# SCH_Sensor_circuit_design_2023-04-27.net
KiCad netlist of a schematic drawn in EasyEDA
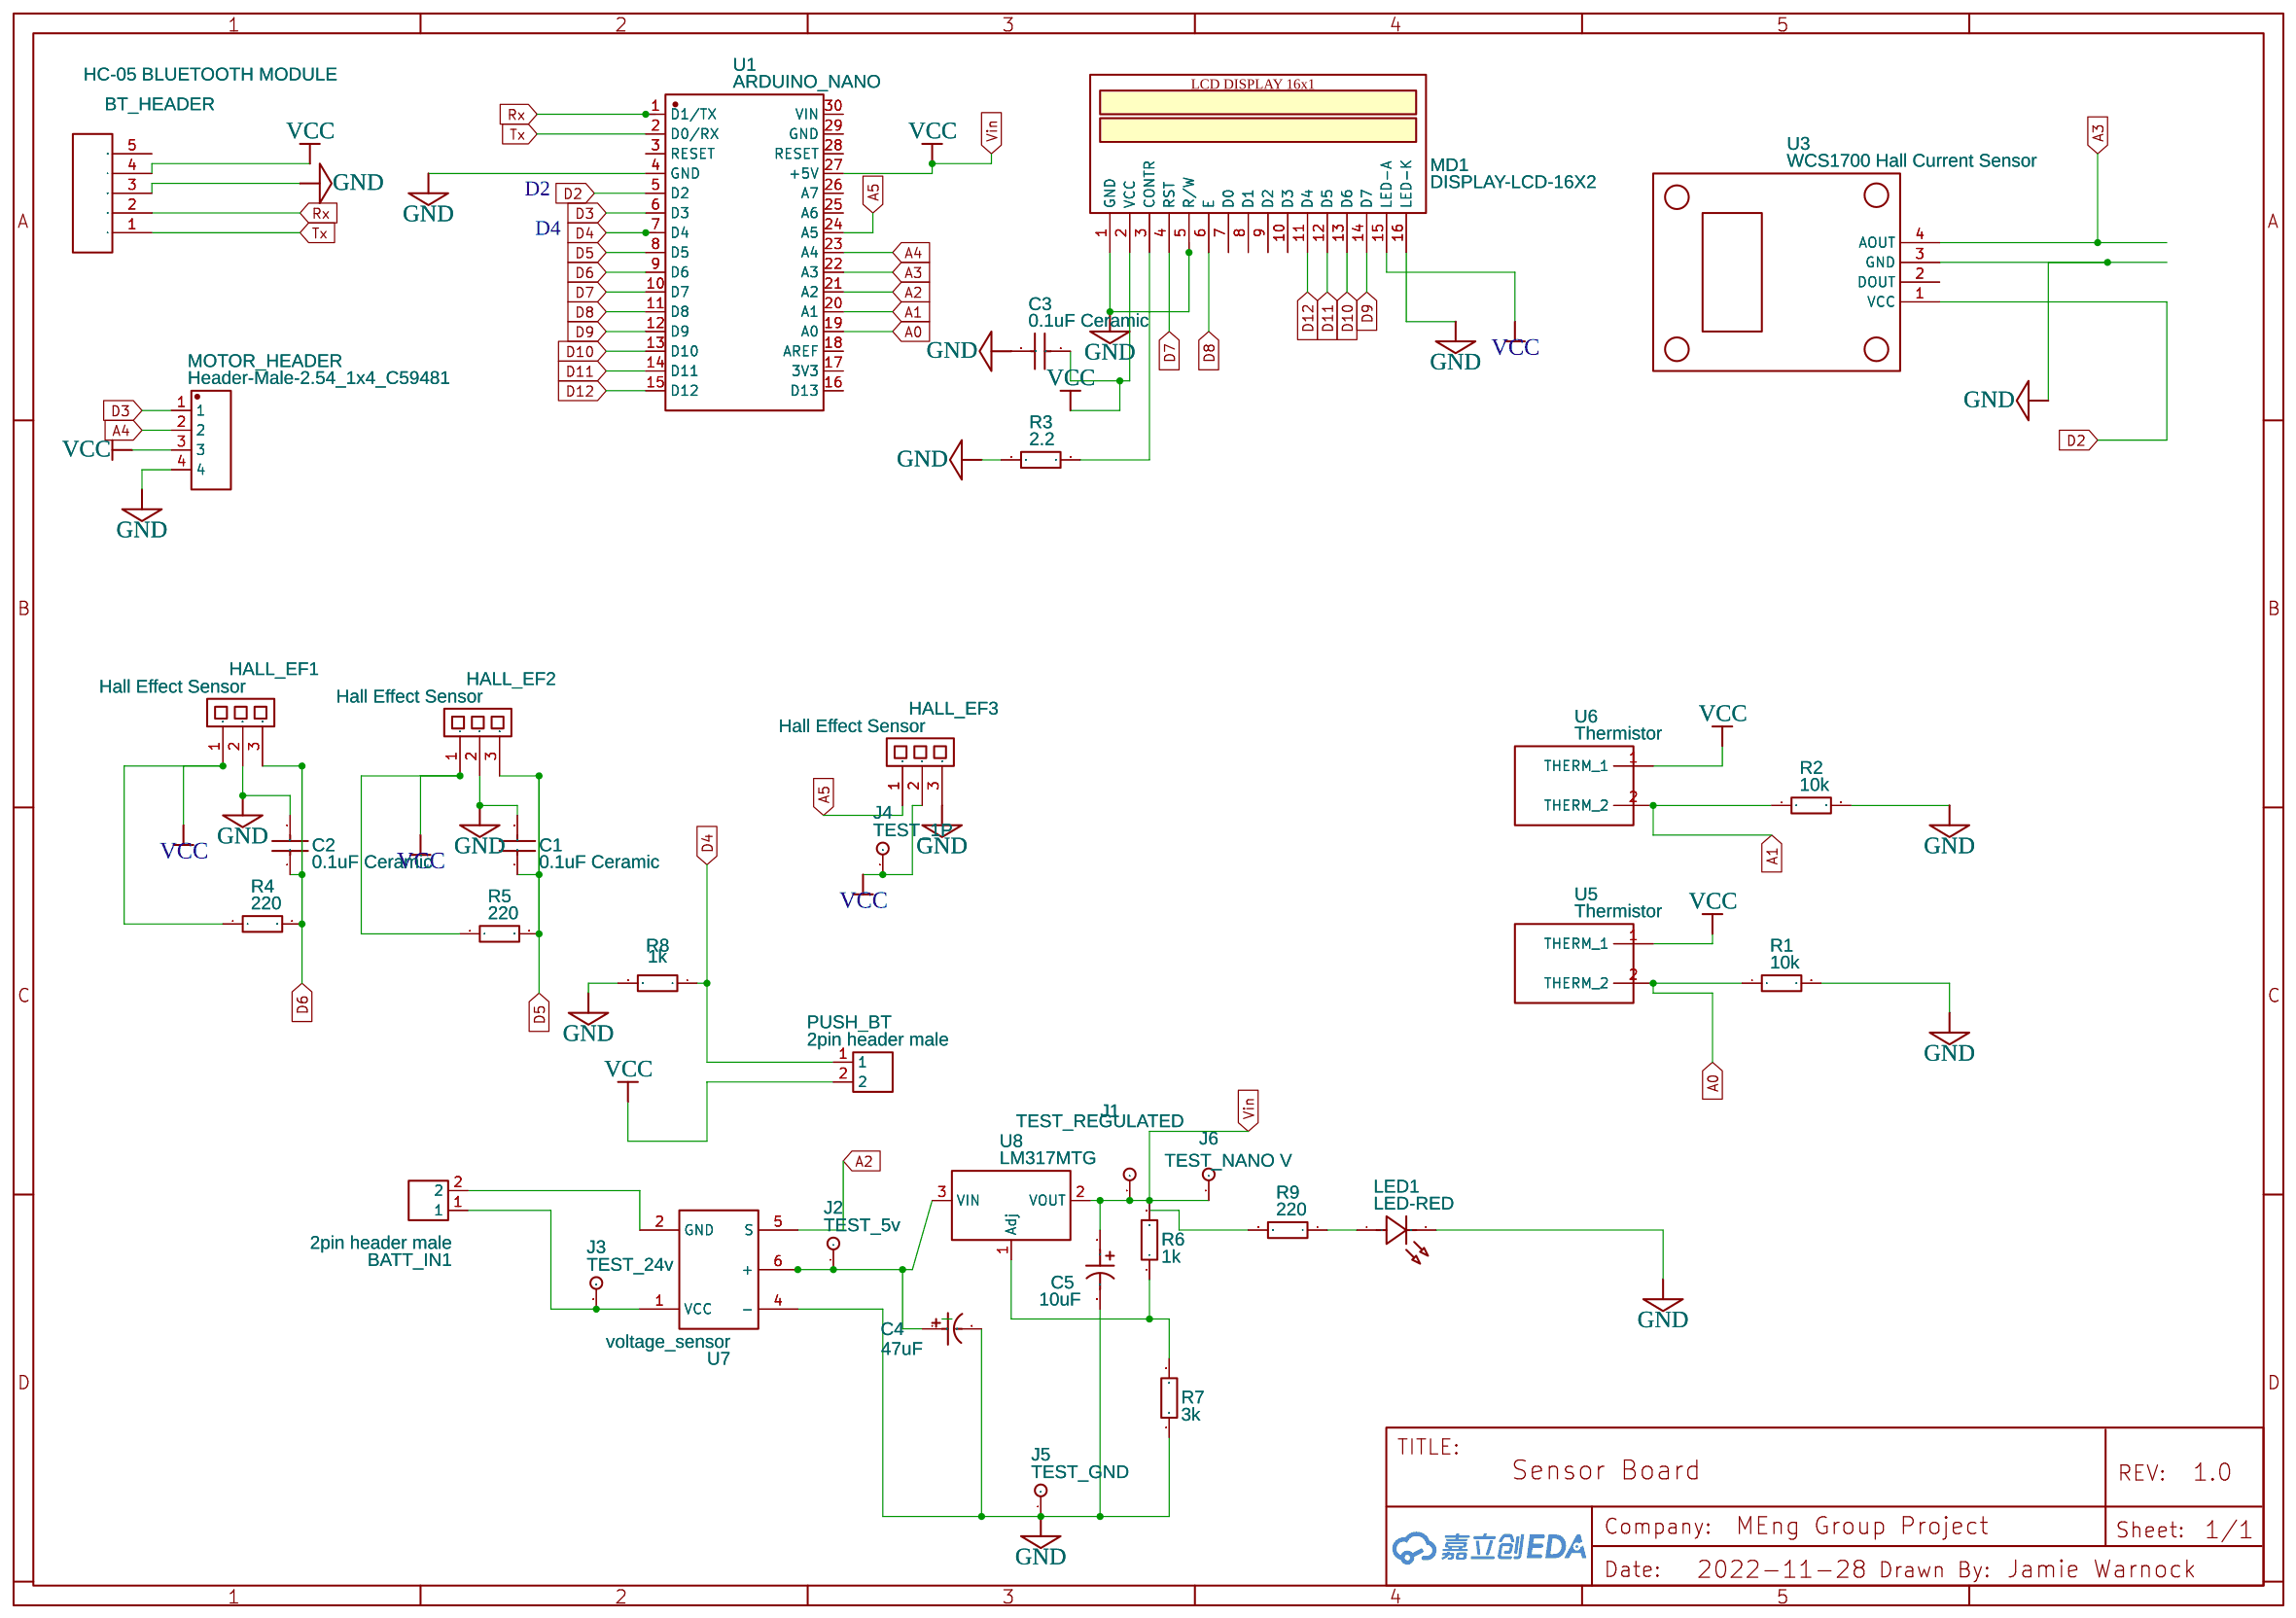
[diagram p0: schematic sheet]

(export (version "E")
  (design (tool "Eeschema 10.0.6"))
  (components
    (comp (ref "BATT_IN1")
      (value "2pin header male")
      (fields
        (field (name "BOM_Manufacturer Part") "Headers  Pins2.54mm1*10P")
        (field (name "BOM_Supplier Part") "C57369")
      )
      (libsource (lib "") (part "2pin header male"))
    )
    (comp (ref "BT_HEADER")
      (value "HC-05 BLUETOOTH MODULE")
      (fields (field (name "BOM_Manufacturer Part") "New SchematicLib"))
      (libsource (lib "") (part "Female pin header 5 3D"))
    )
    (comp (ref "C1")
      (value "0.1uF Ceramic")
      (fields (field (name "BOM_Manufacturer Part") "Capacitor_Ceramic"))
      (libsource (lib "") (part "Capacitor_Ceramic"))
    )
    (comp (ref "C2")
      (value "0.1uF Ceramic")
      (fields (field (name "BOM_Manufacturer Part") "Capacitor_Ceramic"))
      (libsource (lib "") (part "Capacitor_Ceramic"))
    )
    (comp (ref "C3")
      (value "0.1uF Ceramic")
      (fields (field (name "BOM_Manufacturer Part") "Capacitor_Ceramic"))
      (libsource (lib "") (part "Capacitor_Ceramic_1"))
    )
    (comp (ref "C4")
      (value "47uF")
      (fields (field (name "BOM_Manufacturer Part") "47uF 100V") (field (name "BOM_Supplier Part") "C36473"))
      (libsource (lib "") (part "v 47uF 100V"))
    )
    (comp (ref "C5")
      (value "10uF")
      (fields
        (field (name "BOM_Manufacturer Part") "50V10uF CD110")
        (field (name "BOM_Supplier Part") "C2960373")
      )
      (libsource (lib "") (part "50V10UF CD110_C2960373"))
    )
    (comp (ref "HALL_EF1") (value "Hall Effect Sensor") (libsource (lib "") (part "HEADER MALE 1X3")))
    (comp (ref "HALL_EF2") (value "Hall Effect Sensor") (libsource (lib "") (part "HEADER MALE 1X3")))
    (comp (ref "HALL_EF3") (value "Hall Effect Sensor") (libsource (lib "") (part "HEADER MALE 1X3")))
    (comp (ref "J1") (value "TEST_REGULATED") (libsource (lib "") (part "TEST_1P")))
    (comp (ref "J2") (value "TEST_5v") (libsource (lib "") (part "TEST_1P")))
    (comp (ref "J3") (value "TEST_24v") (libsource (lib "") (part "TEST_1P")))
    (comp (ref "J4") (value "TEST_1P") (libsource (lib "") (part "TEST_1P")))
    (comp (ref "J5") (value "TEST_GND") (libsource (lib "") (part "TEST_1P")))
    (comp (ref "J6") (value "TEST_NANO V") (libsource (lib "") (part "TEST_1P")))
    (comp (ref "LED1")
      (value "LED-RED")
      (fields (field (name "BOM_Manufacturer Part") "264-7ID") (field (name "BOM_Supplier Part") "C605466"))
      (libsource (lib "") (part "LED-RED"))
    )
    (comp (ref "MD1") (value "DISPLAY-LCD-16X2") (libsource (lib "") (part "DISPLAY-LCD-16X2")))
    (comp (ref "MOTOR_HEADER")
      (value "Header-Male-2.54_1x4_C59481")
      (fields
        (field (name "BOM_Manufacturer Part") "Headers  Pins 1*4P")
        (field (name "BOM_Supplier Part") "C59481")
      )
      (libsource (lib "") (part "Header-Male-2.54_1x4_C59481"))
    )
    (comp (ref "PUSH_BT")
      (value "2pin header male")
      (fields
        (field (name "BOM_Manufacturer Part") "Headers  Pins2.54mm1*10P")
        (field (name "BOM_Supplier Part") "C57369")
      )
      (libsource (lib "") (part "2pin header male_1"))
    )
    (comp (ref "R1")
      (value "10k")
      (fields
        (field (name "BOM_Manufacturer Part") "EWWR0003J15R0T9")
        (field (name "BOM_Supplier Part") "C348853")
      )
      (libsource (lib "") (part "EWWR0003J15R0T9_1"))
    )
    (comp (ref "R2")
      (value "10k")
      (fields
        (field (name "BOM_Manufacturer Part") "EWWR0003J15R0T9")
        (field (name "BOM_Supplier Part") "C348853")
      )
      (libsource (lib "") (part "EWWR0003J15R0T9_1"))
    )
    (comp (ref "R3")
      (value "2.2")
      (fields
        (field (name "BOM_Manufacturer Part") "EWWR0003J2R20T9")
        (field (name "BOM_Supplier Part") "C348866")
      )
      (libsource (lib "") (part "EWWR0003J2R20T9"))
    )
    (comp (ref "R4")
      (value "220")
      (fields
        (field (name "BOM_Manufacturer Part") "EWWR0003J15R0T9")
        (field (name "BOM_Supplier Part") "C348853")
      )
      (libsource (lib "") (part "EWWR0003J15R0T9_1"))
    )
    (comp (ref "R5")
      (value "220")
      (fields
        (field (name "BOM_Manufacturer Part") "EWWR0003J15R0T9")
        (field (name "BOM_Supplier Part") "C348853")
      )
      (libsource (lib "") (part "EWWR0003J15R0T9_1"))
    )
    (comp (ref "R6")
      (value "1k")
      (fields
        (field (name "BOM_Manufacturer Part") "EWWR0003J15R0T9")
        (field (name "BOM_Supplier Part") "C348853")
      )
      (libsource (lib "") (part "EWWR0003J15R0T9_2"))
    )
    (comp (ref "R7")
      (value "3k")
      (fields
        (field (name "BOM_Manufacturer Part") "EWWR0003J15R0T9")
        (field (name "BOM_Supplier Part") "C348853")
      )
      (libsource (lib "") (part "EWWR0003J15R0T9_2"))
    )
    (comp (ref "R8")
      (value "1k")
      (fields
        (field (name "BOM_Manufacturer Part") "EWWR0003J15R0T9")
        (field (name "BOM_Supplier Part") "C348853")
      )
      (libsource (lib "") (part "EWWR0003J15R0T9"))
    )
    (comp (ref "R9")
      (value "220")
      (fields
        (field (name "BOM_Manufacturer Part") "EWWR0003J15R0T9")
        (field (name "BOM_Supplier Part") "C348853")
      )
      (libsource (lib "") (part "EWWR0003J15R0T9"))
    )
    (comp (ref "U1")
      (value "ARDUINO_NANO")
      (fields (field (name "BOM_Supplier Part") "C9900017879"))
      (libsource (lib "") (part "ARDUINO_NANO"))
    )
    (comp (ref "U3")
      (value "WCS1700 Hall Current Sensor")
      (fields (field (name "BOM_Supplier Part") "WCS1700"))
      (libsource (lib "") (part "WCS1700 Hall Current Sensor"))
    )
    (comp (ref "U5") (value "Thermistor") (libsource (lib "") (part "Thermistor")))
    (comp (ref "U6") (value "Thermistor") (libsource (lib "") (part "Thermistor")))
    (comp (ref "U7")
      (value "voltage_sensor")
      (fields
        (field (name "BOM_Manufacturer Part") "NMH1212SC")
        (field (name "BOM_Supplier Part") "811-1518-5-ND")
      )
      (libsource (lib "") (part "voltage_sensor"))
    )
    (comp (ref "U8")
      (value "LM317MTG")
      (fields (field (name "BOM_Supplier Part") "C907009"))
      (libsource (lib "") (part "LM317MTG"))
    )
  )
  (nets
    (net (code "1") (name "A0") (class "Default")
      (node (ref "R1") (pin "1") (pinfunction "1_1") (pintype "unspecified"))
      (node (ref "U1") (pin "19") (pinfunction "A0_19") (pintype "unspecified"))
      (node (ref "U5") (pin "2") (pinfunction "THERM_2_2") (pintype "unspecified"))
    )
    (net (code "2") (name "A1") (class "Default")
      (node (ref "R2") (pin "1") (pinfunction "1_1") (pintype "unspecified"))
      (node (ref "U1") (pin "20") (pinfunction "A1_20") (pintype "unspecified"))
      (node (ref "U6") (pin "2") (pinfunction "THERM_2_2") (pintype "unspecified"))
    )
    (net (code "3") (name "A2") (class "Default")
      (node (ref "U1") (pin "21") (pinfunction "A2_21") (pintype "unspecified"))
      (node (ref "U7") (pin "5") (pinfunction "S_5") (pintype "unspecified"))
    )
    (net (code "4") (name "A3") (class "Default")
      (node (ref "U1") (pin "22") (pinfunction "A3_22") (pintype "unspecified"))
      (node (ref "U3") (pin "4") (pinfunction "AOUT_4") (pintype "unspecified"))
    )
    (net (code "5") (name "A4") (class "Default")
      (node (ref "MOTOR_HEADER") (pin "2") (pinfunction "2_2") (pintype "unspecified"))
      (node (ref "U1") (pin "23") (pinfunction "A4_23") (pintype "unspecified"))
    )
    (net (code "6") (name "A5") (class "Default")
      (node (ref "HALL_EF3") (pin "1") (pinfunction "1_1") (pintype "unspecified"))
      (node (ref "U1") (pin "24") (pinfunction "A5_24") (pintype "unspecified"))
    )
    (net (code "7") (name "D2") (class "Default")
      (node (ref "U1") (pin "5") (pinfunction "D2_5") (pintype "unspecified"))
      (node (ref "U3") (pin "1") (pinfunction "VCC_1") (pintype "unspecified"))
    )
    (net (code "8") (name "D3") (class "Default")
      (node (ref "MOTOR_HEADER") (pin "1") (pinfunction "1_1") (pintype "unspecified"))
      (node (ref "U1") (pin "6") (pinfunction "D3_6") (pintype "unspecified"))
    )
    (net (code "9") (name "D4") (class "Default")
      (node (ref "PUSH_BT") (pin "1") (pinfunction "1_1") (pintype "unspecified"))
      (node (ref "R8") (pin "1") (pinfunction "1_1") (pintype "unspecified"))
      (node (ref "U1") (pin "7") (pinfunction "D4_7") (pintype "unspecified"))
    )
    (net (code "10") (name "D5") (class "Default")
      (node (ref "C1") (pin "1") (pinfunction "1_1") (pintype "unspecified"))
      (node (ref "HALL_EF2") (pin "3") (pinfunction "3_3") (pintype "unspecified"))
      (node (ref "R5") (pin "2") (pinfunction "2_2") (pintype "unspecified"))
      (node (ref "U1") (pin "8") (pinfunction "D5_8") (pintype "unspecified"))
    )
    (net (code "11") (name "D6") (class "Default")
      (node (ref "C2") (pin "1") (pinfunction "1_1") (pintype "unspecified"))
      (node (ref "HALL_EF1") (pin "3") (pinfunction "3_3") (pintype "unspecified"))
      (node (ref "R4") (pin "2") (pinfunction "2_2") (pintype "unspecified"))
      (node (ref "U1") (pin "9") (pinfunction "D6_9") (pintype "unspecified"))
    )
    (net (code "12") (name "D7") (class "Default")
      (node (ref "MD1") (pin "4") (pinfunction "RST_4") (pintype "unspecified"))
      (node (ref "U1") (pin "10") (pinfunction "D7_10") (pintype "unspecified"))
    )
    (net (code "13") (name "D8") (class "Default")
      (node (ref "MD1") (pin "6") (pinfunction "E_6") (pintype "unspecified"))
      (node (ref "U1") (pin "11") (pinfunction "D8_11") (pintype "unspecified"))
    )
    (net (code "14") (name "D9") (class "Default")
      (node (ref "MD1") (pin "14") (pinfunction "D7_14") (pintype "unspecified"))
      (node (ref "U1") (pin "12") (pinfunction "D9_12") (pintype "unspecified"))
    )
    (net (code "15") (name "D10") (class "Default")
      (node (ref "MD1") (pin "13") (pinfunction "D6_13") (pintype "unspecified"))
      (node (ref "U1") (pin "13") (pinfunction "D10_13") (pintype "unspecified"))
    )
    (net (code "16") (name "D11") (class "Default")
      (node (ref "MD1") (pin "12") (pinfunction "D5_12") (pintype "unspecified"))
      (node (ref "U1") (pin "14") (pinfunction "D11_14") (pintype "unspecified"))
    )
    (net (code "17") (name "D12") (class "Default")
      (node (ref "MD1") (pin "11") (pinfunction "D4_11") (pintype "unspecified"))
      (node (ref "U1") (pin "15") (pinfunction "D12_15") (pintype "unspecified"))
    )
    (net (code "18") (name "GND") (class "Default")
      (node (ref "BT_HEADER") (pin "3") (pinfunction "3_3") (pintype "unspecified"))
      (node (ref "C1") (pin "2") (pinfunction "2_2") (pintype "unspecified"))
      (node (ref "C2") (pin "2") (pinfunction "2_2") (pintype "unspecified"))
      (node (ref "C3") (pin "1") (pinfunction "1_1") (pintype "unspecified"))
      (node (ref "C4") (pin "2") (pinfunction "2_2") (pintype "input"))
      (node (ref "C5") (pin "2") (pinfunction "2_2") (pintype "input"))
      (node (ref "HALL_EF1") (pin "2") (pinfunction "2_2") (pintype "unspecified"))
      (node (ref "HALL_EF2") (pin "2") (pinfunction "2_2") (pintype "unspecified"))
      (node (ref "HALL_EF3") (pin "3") (pinfunction "3_3") (pintype "unspecified"))
      (node (ref "J5") (pin "1") (pinfunction "1_1") (pintype "unspecified"))
      (node (ref "LED1") (pin "2") (pinfunction "K_2") (pintype "unspecified"))
      (node (ref "MD1") (pin "1") (pinfunction "GND_1") (pintype "unspecified"))
      (node (ref "MD1") (pin "16") (pinfunction "LED-K_16") (pintype "unspecified"))
      (node (ref "MD1") (pin "5") (pinfunction "R/W_5") (pintype "unspecified"))
      (node (ref "MOTOR_HEADER") (pin "4") (pinfunction "4_4") (pintype "unspecified"))
      (node (ref "R1") (pin "2") (pinfunction "2_2") (pintype "unspecified"))
      (node (ref "R2") (pin "2") (pinfunction "2_2") (pintype "unspecified"))
      (node (ref "R3") (pin "1") (pinfunction "1_1") (pintype "unspecified"))
      (node (ref "R7") (pin "1") (pinfunction "1_1") (pintype "unspecified"))
      (node (ref "R8") (pin "2") (pinfunction "2_2") (pintype "unspecified"))
      (node (ref "U1") (pin "4") (pinfunction "GND_4") (pintype "unspecified"))
      (node (ref "U3") (pin "3") (pinfunction "GND_3") (pintype "unspecified"))
      (node (ref "U7") (pin "4") (pinfunction "-_4") (pintype "unspecified"))
    )
    (net (code "19") (name "Net-(LED1-A)") (class "Default")
      (node (ref "LED1") (pin "1") (pinfunction "A_1") (pintype "unspecified"))
      (node (ref "R9") (pin "1") (pinfunction "1_1") (pintype "unspecified"))
    )
    (net (code "20") (name "Net-(MD1-CONTR)") (class "Default")
      (node (ref "MD1") (pin "3") (pinfunction "CONTR_3") (pintype "unspecified"))
      (node (ref "R3") (pin "2") (pinfunction "2_2") (pintype "unspecified"))
    )
    (net (code "21") (name "Net-(U7-+)") (class "Default")
      (node (ref "C4") (pin "1") (pinfunction "1_1") (pintype "input"))
      (node (ref "J2") (pin "1") (pinfunction "1_1") (pintype "unspecified"))
      (node (ref "U7") (pin "6") (pinfunction "+_6") (pintype "unspecified"))
      (node (ref "U8") (pin "3") (pinfunction "VIN_3") (pintype "unspecified"))
    )
    (net (code "22") (name "Net-(U7-GND)") (class "Default")
      (node (ref "BATT_IN1") (pin "2") (pinfunction "2_2") (pintype "unspecified"))
      (node (ref "U7") (pin "2") (pinfunction "GND_2") (pintype "unspecified"))
    )
    (net (code "23") (name "Net-(U7-VCC)") (class "Default")
      (node (ref "BATT_IN1") (pin "1") (pinfunction "1_1") (pintype "unspecified"))
      (node (ref "J3") (pin "1") (pinfunction "1_1") (pintype "unspecified"))
      (node (ref "U7") (pin "1") (pinfunction "VCC_1") (pintype "unspecified"))
    )
    (net (code "24") (name "Net-(U8-Adj)") (class "Default")
      (node (ref "R6") (pin "1") (pinfunction "1_1") (pintype "unspecified"))
      (node (ref "R7") (pin "2") (pinfunction "2_2") (pintype "unspecified"))
      (node (ref "U8") (pin "1") (pinfunction "Adj_1") (pintype "unspecified"))
    )
    (net (code "25") (name "Rx") (class "Default")
      (node (ref "BT_HEADER") (pin "2") (pinfunction "2_2") (pintype "unspecified"))
      (node (ref "U1") (pin "1") (pinfunction "D1/TX_1") (pintype "unspecified"))
    )
    (net (code "26") (name "Tx") (class "Default")
      (node (ref "BT_HEADER") (pin "1") (pinfunction "1_1") (pintype "unspecified"))
      (node (ref "U1") (pin "2") (pinfunction "D0/RX_2") (pintype "unspecified"))
    )
    (net (code "27") (name "Vin") (class "Default")
      (node (ref "BT_HEADER") (pin "4") (pinfunction "4_4") (pintype "unspecified"))
      (node (ref "C3") (pin "2") (pinfunction "2_2") (pintype "unspecified"))
      (node (ref "C5") (pin "1") (pinfunction "1_1") (pintype "input"))
      (node (ref "HALL_EF1") (pin "1") (pinfunction "1_1") (pintype "unspecified"))
      (node (ref "HALL_EF2") (pin "1") (pinfunction "1_1") (pintype "unspecified"))
      (node (ref "HALL_EF3") (pin "2") (pinfunction "2_2") (pintype "unspecified"))
      (node (ref "J1") (pin "1") (pinfunction "1_1") (pintype "unspecified"))
      (node (ref "J4") (pin "1") (pinfunction "1_1") (pintype "unspecified"))
      (node (ref "J6") (pin "1") (pinfunction "1_1") (pintype "unspecified"))
      (node (ref "MD1") (pin "15") (pinfunction "LED-A_15") (pintype "unspecified"))
      (node (ref "MD1") (pin "2") (pinfunction "VCC_2") (pintype "unspecified"))
      (node (ref "MOTOR_HEADER") (pin "3") (pinfunction "3_3") (pintype "unspecified"))
      (node (ref "PUSH_BT") (pin "2") (pinfunction "2_2") (pintype "unspecified"))
      (node (ref "R4") (pin "1") (pinfunction "1_1") (pintype "unspecified"))
      (node (ref "R5") (pin "1") (pinfunction "1_1") (pintype "unspecified"))
      (node (ref "R6") (pin "2") (pinfunction "2_2") (pintype "unspecified"))
      (node (ref "R9") (pin "2") (pinfunction "2_2") (pintype "unspecified"))
      (node (ref "U1") (pin "27") (pinfunction "+5V_27") (pintype "unspecified"))
      (node (ref "U5") (pin "1") (pinfunction "THERM_1_1") (pintype "unspecified"))
      (node (ref "U6") (pin "1") (pinfunction "THERM_1_1") (pintype "unspecified"))
      (node (ref "U8") (pin "2") (pinfunction "VOUT_2") (pintype "unspecified"))
    )
    (net (code "28") (name "unconnected-(BT_HEADER-Pad5)") (class "Default")
      (node (ref "BT_HEADER") (pin "5") (pinfunction "5_5") (pintype "unspecified"))
    )
    (net (code "29") (name "unconnected-(MD1-D0-Pad7)") (class "Default")
      (node (ref "MD1") (pin "7") (pinfunction "D0_7") (pintype "unspecified"))
    )
    (net (code "30") (name "unconnected-(MD1-D1-Pad8)") (class "Default")
      (node (ref "MD1") (pin "8") (pinfunction "D1_8") (pintype "unspecified"))
    )
    (net (code "31") (name "unconnected-(MD1-D2-Pad9)") (class "Default")
      (node (ref "MD1") (pin "9") (pinfunction "D2_9") (pintype "unspecified"))
    )
    (net (code "32") (name "unconnected-(MD1-D3-Pad10)") (class "Default")
      (node (ref "MD1") (pin "10") (pinfunction "D3_10") (pintype "unspecified"))
    )
    (net (code "33") (name "unconnected-(U1-3V3-Pad17)") (class "Default")
      (node (ref "U1") (pin "17") (pinfunction "3V3_17") (pintype "unspecified"))
    )
    (net (code "34") (name "unconnected-(U1-A6-Pad25)") (class "Default")
      (node (ref "U1") (pin "25") (pinfunction "A6_25") (pintype "unspecified"))
    )
    (net (code "35") (name "unconnected-(U1-A7-Pad26)") (class "Default")
      (node (ref "U1") (pin "26") (pinfunction "A7_26") (pintype "unspecified"))
    )
    (net (code "36") (name "unconnected-(U1-AREF-Pad18)") (class "Default")
      (node (ref "U1") (pin "18") (pinfunction "AREF_18") (pintype "unspecified"))
    )
    (net (code "37") (name "unconnected-(U1-D13-Pad16)") (class "Default")
      (node (ref "U1") (pin "16") (pinfunction "D13_16") (pintype "unspecified"))
    )
    (net (code "38") (name "unconnected-(U1-GND-Pad29)") (class "Default")
      (node (ref "U1") (pin "29") (pinfunction "GND_29") (pintype "unspecified"))
    )
    (net (code "39") (name "unconnected-(U1-RESET-Pad3)") (class "Default")
      (node (ref "U1") (pin "3") (pinfunction "RESET_3") (pintype "unspecified"))
    )
    (net (code "40") (name "unconnected-(U1-RESET-Pad28)") (class "Default")
      (node (ref "U1") (pin "28") (pinfunction "RESET_28") (pintype "unspecified"))
    )
    (net (code "41") (name "unconnected-(U1-VIN-Pad30)") (class "Default")
      (node (ref "U1") (pin "30") (pinfunction "VIN_30") (pintype "unspecified"))
    )
    (net (code "42") (name "unconnected-(U3-DOUT-Pad2)") (class "Default")
      (node (ref "U3") (pin "2") (pinfunction "DOUT_2") (pintype "unspecified"))
    )
  )
)
